# PSU.net
KiCad netlist of a schematic drawn in EAGLE
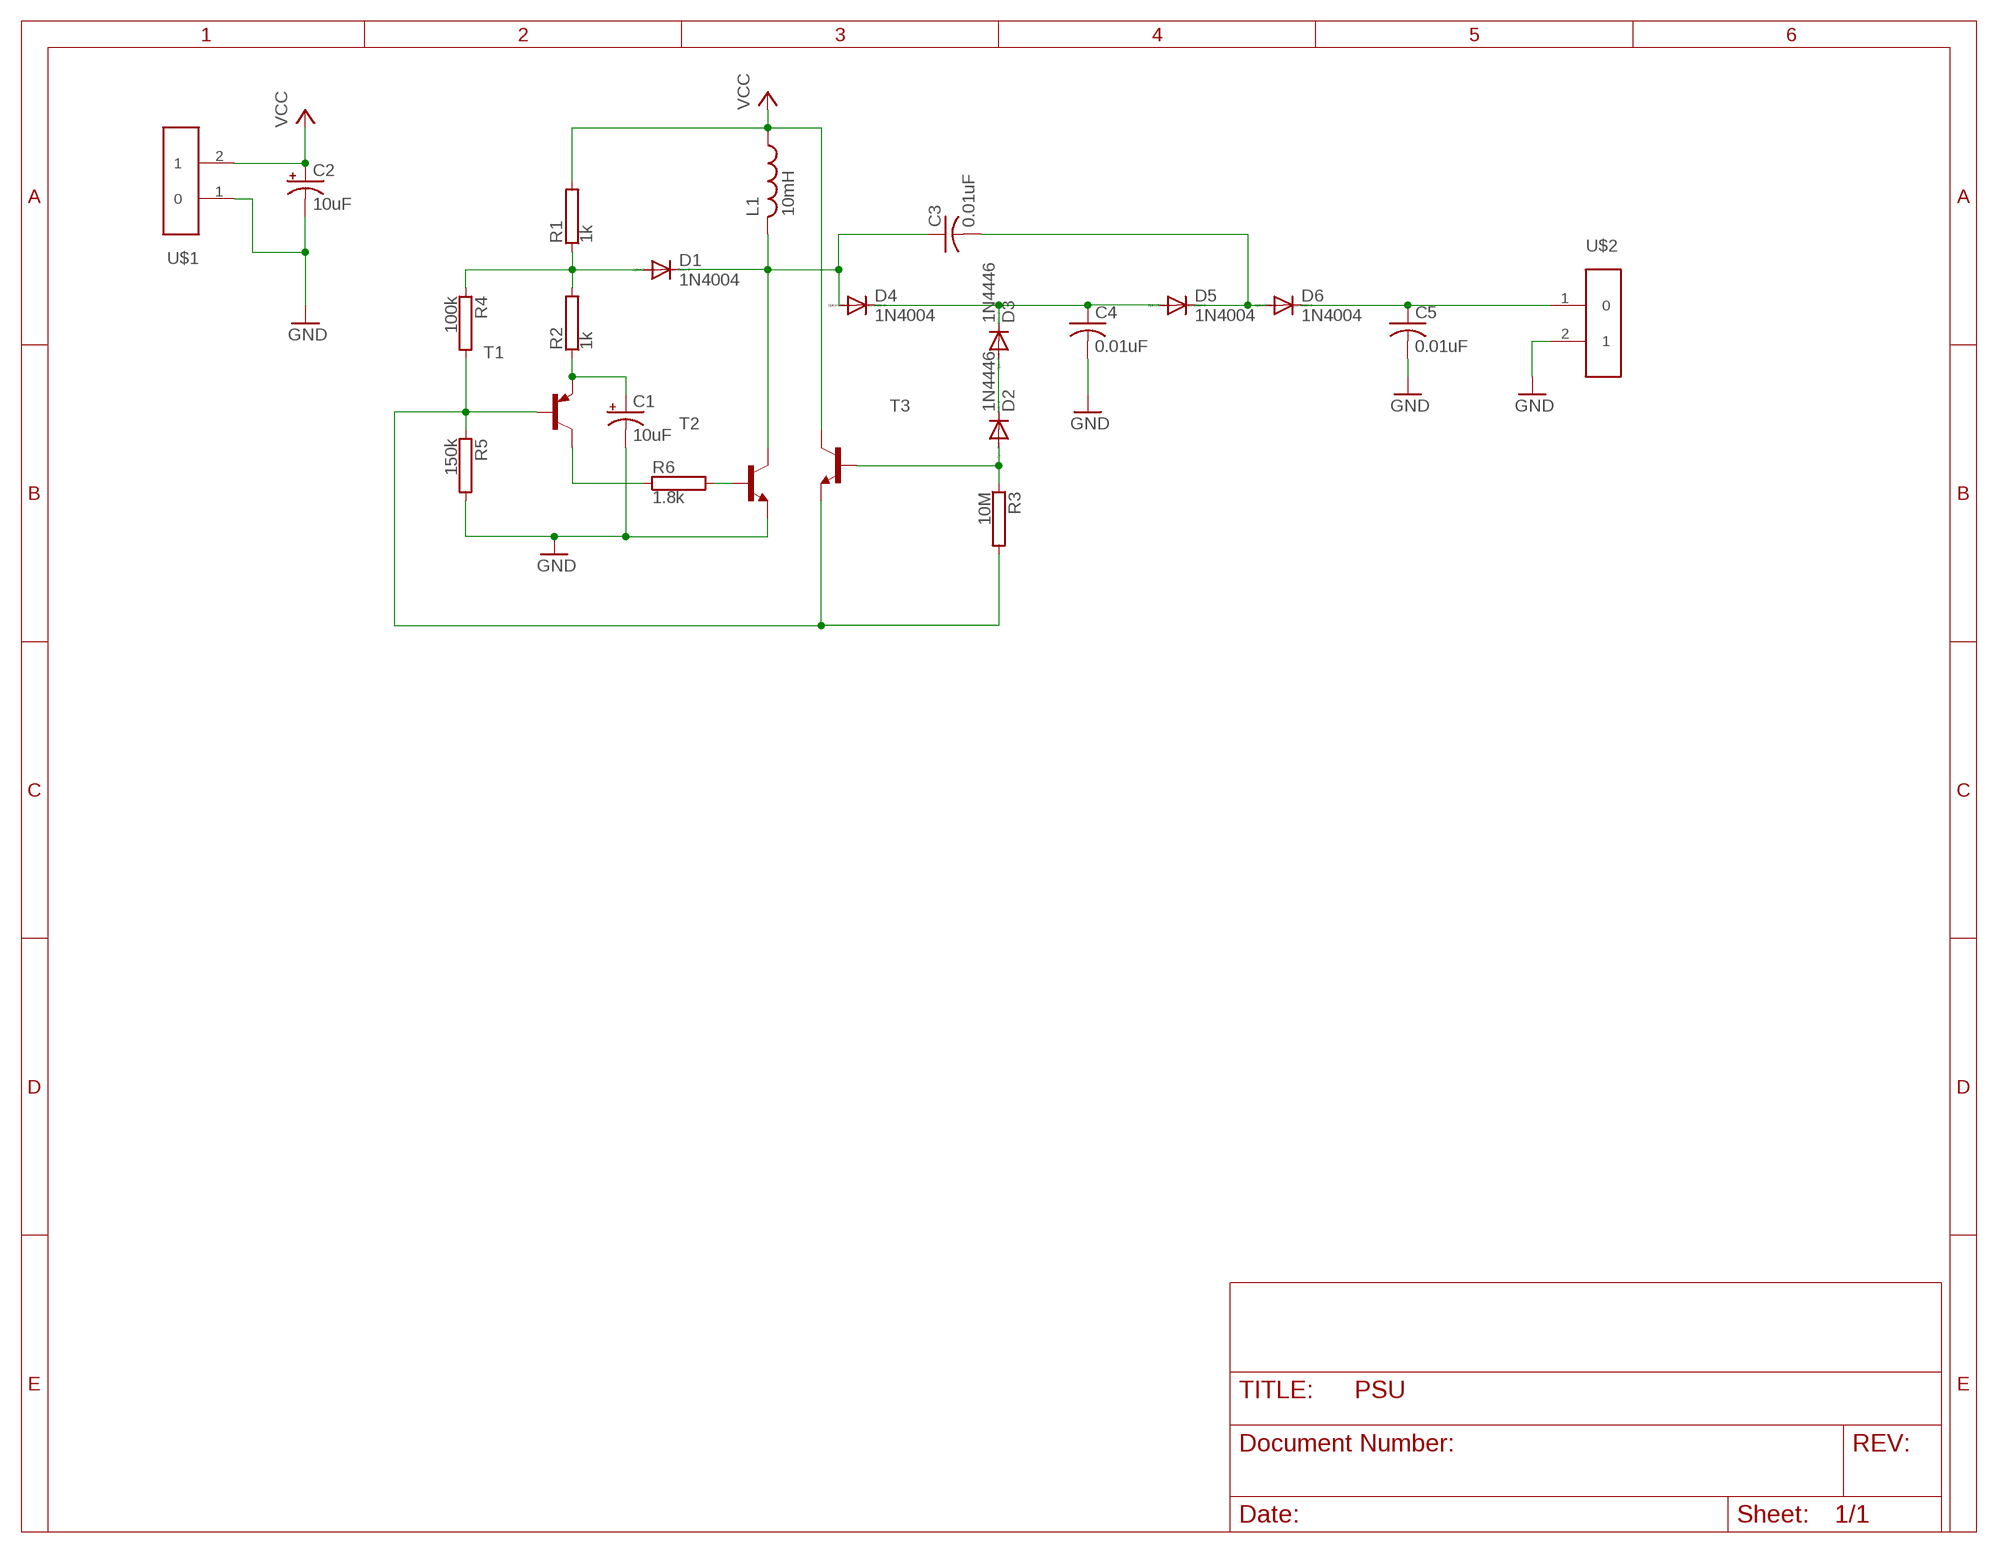
[diagram p0: schematic, sheet 1]

(export (version "E")
  (design (tool "Eeschema 10.0.6"))
  (components
    (comp (ref "C1")
      (value "10uF")
      (footprint "eagle-import:E2,5-5")
      (libsource (lib "eagle-import") (part "CPOL-USE2.5-5"))
    )
    (comp (ref "C2")
      (value "10uF")
      (footprint "eagle-import:E2,5-5")
      (libsource (lib "eagle-import") (part "CPOL-USE2.5-5"))
    )
    (comp (ref "C3")
      (value "0.01uF")
      (footprint "eagle-import:C075-032X103")
      (libsource (lib "eagle-import") (part "C-US075-032X103"))
    )
    (comp (ref "C4")
      (value "0.01uF")
      (footprint "eagle-import:C075-032X103")
      (libsource (lib "eagle-import") (part "C-US075-032X103"))
    )
    (comp (ref "C5")
      (value "0.01uF")
      (footprint "eagle-import:C075-032X103")
      (libsource (lib "eagle-import") (part "C-US075-032X103"))
    )
    (comp (ref "D1")
      (value "1N4004")
      (footprint "eagle-import:DO41-10")
      (libsource (lib "eagle-import") (part "1N4004"))
    )
    (comp (ref "D2")
      (value "1N4446")
      (footprint "eagle-import:DO35-10")
      (libsource (lib "eagle-import") (part "1N4446"))
    )
    (comp (ref "D3")
      (value "1N4446")
      (footprint "eagle-import:DO35-10")
      (libsource (lib "eagle-import") (part "1N4446"))
    )
    (comp (ref "D4")
      (value "1N4004")
      (footprint "eagle-import:DO41-10")
      (libsource (lib "eagle-import") (part "1N4004"))
    )
    (comp (ref "D5")
      (value "1N4004")
      (footprint "eagle-import:DO41-10")
      (libsource (lib "eagle-import") (part "1N4004"))
    )
    (comp (ref "D6")
      (value "1N4004")
      (footprint "eagle-import:DO41-10")
      (libsource (lib "eagle-import") (part "1N4004"))
    )
    (comp (ref "L1")
      (value "10mH")
      (footprint "eagle-import:0207_5V")
      (libsource (lib "eagle-import") (part "L-US0207/5V"))
    )
    (comp (ref "R1")
      (value "1k")
      (footprint "eagle-import:RS1_4")
      (fields (field (name "MF") "OHMITE") (field (name "MPN") "RRS1K0"))
      (libsource (lib "eagle-import") (part "RRS1/4"))
    )
    (comp (ref "R2")
      (value "1k")
      (footprint "eagle-import:RS1_4")
      (fields (field (name "MF") "OHMITE") (field (name "MPN") "RRS1K0"))
      (libsource (lib "eagle-import") (part "RRS1/4"))
    )
    (comp (ref "R3")
      (value "10M")
      (footprint "eagle-import:RS1_4")
      (fields (field (name "MF") "OHMITE") (field (name "MPN") "RRS1K0"))
      (libsource (lib "eagle-import") (part "RRS1/4"))
    )
    (comp (ref "R4")
      (value "100k")
      (footprint "eagle-import:RS1_4")
      (fields (field (name "MF") "OHMITE") (field (name "MPN") "RRS1K0"))
      (libsource (lib "eagle-import") (part "RRS1/4"))
    )
    (comp (ref "R5")
      (value "150k")
      (footprint "eagle-import:RS1_4")
      (fields (field (name "MF") "OHMITE") (field (name "MPN") "RRS1K0"))
      (libsource (lib "eagle-import") (part "RRS1/4"))
    )
    (comp (ref "R6")
      (value "1.8k")
      (footprint "eagle-import:RS1_4")
      (fields (field (name "MF") "OHMITE") (field (name "MPN") "RRS1K0"))
      (libsource (lib "eagle-import") (part "RRS1/4"))
    )
    (comp (ref "T1")
      (value "2N4403-PNP-TO92-EBC")
      (footprint "eagle-import:TO92-EBC")
      (libsource (lib "eagle-import") (part "-PNP-TO92-EBC2N4403"))
    )
    (comp (ref "T2")
      (value "MPSA42-NPN-TO92-EBC")
      (footprint "eagle-import:TO92-EBC")
      (libsource (lib "eagle-import") (part "-NPN-TO92-EBCMPSA42"))
    )
    (comp (ref "T3")
      (value "MPSA18-NPN-TO92-EBC")
      (footprint "eagle-import:TO92-EBC")
      (libsource (lib "eagle-import") (part "-NPN-TO92-EBCMPSA18"))
    )
    (comp (ref "U$1")
      (value "ED2609")
      (footprint "eagle-import:ED2609")
      (libsource (lib "eagle-import") (part "ED2609"))
    )
    (comp (ref "U$2")
      (value "ED2609")
      (footprint "eagle-import:ED2609")
      (libsource (lib "eagle-import") (part "ED2609"))
    )
  )
  (nets
    (net (code "1") (name "GND") (class "Default")
      (node (ref "C1") (pin "-") (pinfunction "-_-") (pintype "passive"))
      (node (ref "C2") (pin "-") (pinfunction "-_-") (pintype "passive"))
      (node (ref "C4") (pin "2") (pinfunction "2_2") (pintype "passive"))
      (node (ref "C5") (pin "2") (pinfunction "2_2") (pintype "passive"))
      (node (ref "R5") (pin "2") (pinfunction "2_2") (pintype "passive"))
      (node (ref "T2") (pin "E") (pinfunction "E_E") (pintype "passive"))
      (node (ref "U$1") (pin "1") (pinfunction "0_1") (pintype "bidirectional"))
      (node (ref "U$2") (pin "2") (pinfunction "1_2") (pintype "bidirectional"))
    )
    (net (code "2") (name "Net-(C1-Pad+)") (class "Default")
      (node (ref "C1") (pin "+") (pinfunction "+_+") (pintype "passive"))
      (node (ref "R2") (pin "1") (pinfunction "1_1") (pintype "passive"))
      (node (ref "T1") (pin "E") (pinfunction "E_E") (pintype "passive"))
    )
    (net (code "3") (name "Net-(C3-Pad1)") (class "Default")
      (node (ref "C3") (pin "1") (pinfunction "1_1") (pintype "passive"))
      (node (ref "D1") (pin "C") (pinfunction "C_C") (pintype "passive"))
      (node (ref "D4") (pin "A") (pinfunction "A_A") (pintype "passive"))
      (node (ref "L1") (pin "2") (pinfunction "2_2") (pintype "passive"))
      (node (ref "T2") (pin "C") (pinfunction "C_C") (pintype "passive"))
    )
    (net (code "4") (name "Net-(C3-Pad2)") (class "Default")
      (node (ref "C3") (pin "2") (pinfunction "2_2") (pintype "passive"))
      (node (ref "D5") (pin "C") (pinfunction "C_C") (pintype "passive"))
      (node (ref "D6") (pin "A") (pinfunction "A_A") (pintype "passive"))
    )
    (net (code "5") (name "Net-(C4-Pad1)") (class "Default")
      (node (ref "C4") (pin "1") (pinfunction "1_1") (pintype "passive"))
      (node (ref "D3") (pin "C") (pinfunction "C_C") (pintype "passive"))
      (node (ref "D4") (pin "C") (pinfunction "C_C") (pintype "passive"))
      (node (ref "D5") (pin "A") (pinfunction "A_A") (pintype "passive"))
    )
    (net (code "6") (name "Net-(D1-PadA)") (class "Default")
      (node (ref "D1") (pin "A") (pinfunction "A_A") (pintype "passive"))
      (node (ref "R1") (pin "1") (pinfunction "1_1") (pintype "passive"))
      (node (ref "R2") (pin "2") (pinfunction "2_2") (pintype "passive"))
      (node (ref "R4") (pin "1") (pinfunction "1_1") (pintype "passive"))
    )
    (net (code "7") (name "Net-(D2-PadA)") (class "Default")
      (node (ref "D2") (pin "A") (pinfunction "A_A") (pintype "passive"))
      (node (ref "R3") (pin "1") (pinfunction "1_1") (pintype "passive"))
      (node (ref "T3") (pin "B") (pinfunction "B_B") (pintype "passive"))
    )
    (net (code "8") (name "Net-(D2-PadC)") (class "Default")
      (node (ref "D2") (pin "C") (pinfunction "C_C") (pintype "passive"))
      (node (ref "D3") (pin "A") (pinfunction "A_A") (pintype "passive"))
    )
    (net (code "9") (name "Net-(R3-Pad2)") (class "Default")
      (node (ref "R3") (pin "2") (pinfunction "2_2") (pintype "passive"))
      (node (ref "R4") (pin "2") (pinfunction "2_2") (pintype "passive"))
      (node (ref "R5") (pin "1") (pinfunction "1_1") (pintype "passive"))
      (node (ref "T1") (pin "B") (pinfunction "B_B") (pintype "passive"))
      (node (ref "T3") (pin "E") (pinfunction "E_E") (pintype "passive"))
    )
    (net (code "10") (name "Net-(R6-Pad1)") (class "Default")
      (node (ref "R6") (pin "1") (pinfunction "1_1") (pintype "passive"))
      (node (ref "T1") (pin "C") (pinfunction "C_C") (pintype "passive"))
    )
    (net (code "11") (name "Net-(R6-Pad2)") (class "Default")
      (node (ref "R6") (pin "2") (pinfunction "2_2") (pintype "passive"))
      (node (ref "T2") (pin "B") (pinfunction "B_B") (pintype "passive"))
    )
    (net (code "12") (name "Net-(U$2-0)") (class "Default")
      (node (ref "C5") (pin "1") (pinfunction "1_1") (pintype "passive"))
      (node (ref "D6") (pin "C") (pinfunction "C_C") (pintype "passive"))
      (node (ref "U$2") (pin "1") (pinfunction "0_1") (pintype "bidirectional"))
    )
    (net (code "13") (name "VCC") (class "Default")
      (node (ref "C2") (pin "+") (pinfunction "+_+") (pintype "passive"))
      (node (ref "L1") (pin "1") (pinfunction "1_1") (pintype "passive"))
      (node (ref "R1") (pin "2") (pinfunction "2_2") (pintype "passive"))
      (node (ref "T3") (pin "C") (pinfunction "C_C") (pintype "passive"))
      (node (ref "U$1") (pin "2") (pinfunction "1_2") (pintype "bidirectional"))
    )
  )
)
